# as14120_x31_fpga_ttl.net
KiCad netlist of a schematic drawn in Altium Designer
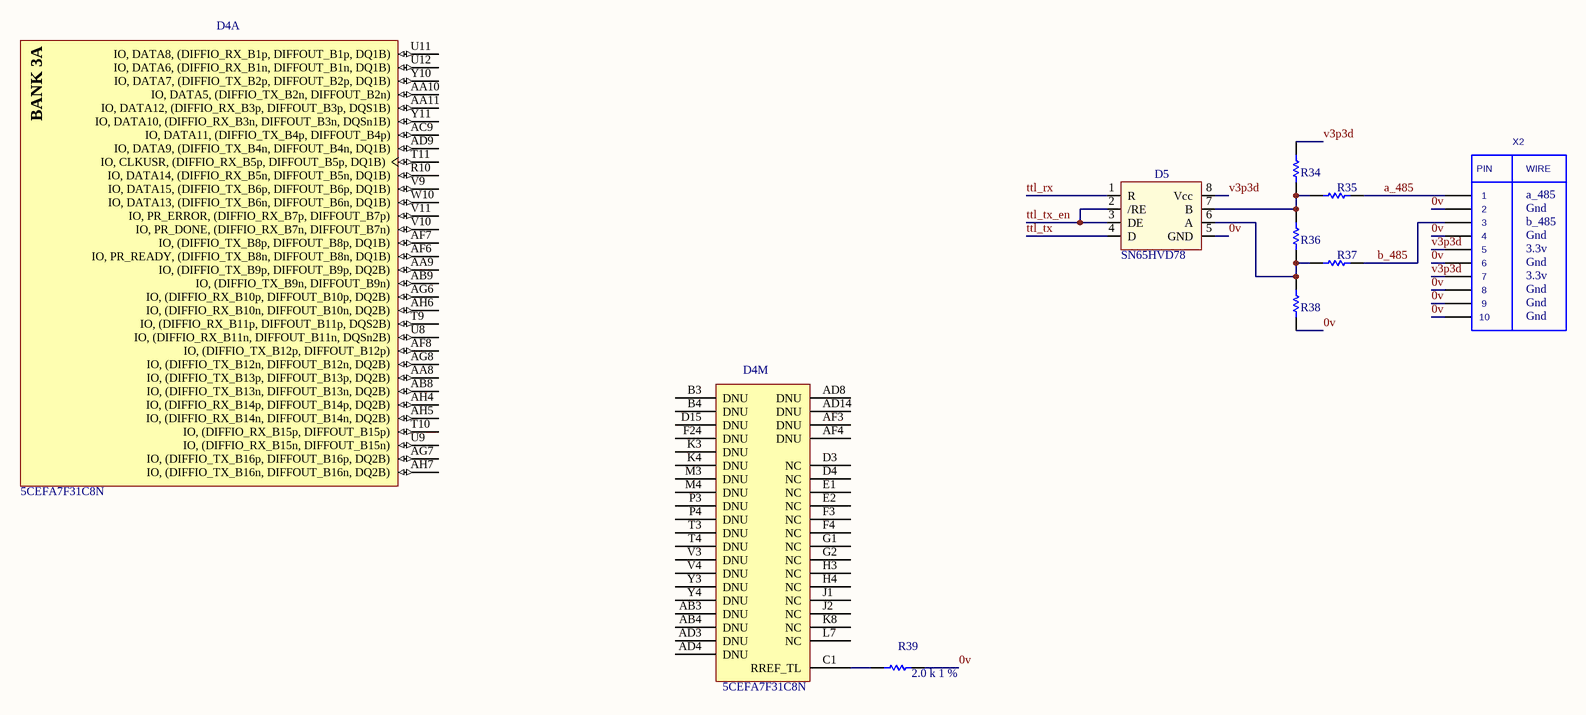
[diagram p0: as14120_x31_fpga_ttl.SchDoc]

(export (version "E")
  (design (tool "Eeschema 10.0.6"))
  (components
    (comp (ref "D4")
      (value "5CEFA7F31C8N")
      (footprint "ALTR-896-FBGA-2000A")
      (fields (field (name "MANUFACTURER") "Altera"))
      (libsource (lib "Altera Cyclone V E") (part "5CEFA7F31C8N"))
    )
    (comp (ref "D5") (value "SN65HVD78") (footprint "8S1_M") (libsource (lib "as14120") (part "SN65HVD78")))
    (comp (ref "R34")
      (value "1K 1% 0805(2012)")
      (footprint "RESC0805(2012)_L")
      (description "1K 0.125W 1% 0805 (2012 Metric)  SMD")
      (fields (field (name "TOLERANCE") "1 %") (field (name "POWER") "0.125 W"))
      (libsource (lib "as14120") (part "RES_0805"))
    )
    (comp (ref "R35")
      (value "1K 1% 0805(2012)")
      (footprint "RESC0805(2012)_L")
      (description "1K 0.125W 1% 0805 (2012 Metric)  SMD")
      (fields (field (name "TOLERANCE") "1 %") (field (name "POWER") "0.125 W"))
      (libsource (lib "as14120") (part "RES_0805"))
    )
    (comp (ref "R36")
      (value "1K 1% 0805(2012)")
      (footprint "RESC0805(2012)_L")
      (description "1K 0.125W 1% 0805 (2012 Metric)  SMD")
      (fields (field (name "TOLERANCE") "1 %") (field (name "POWER") "0.125 W"))
      (libsource (lib "as14120") (part "RES_0805"))
    )
    (comp (ref "R37")
      (value "1K 1% 0805(2012)")
      (footprint "RESC0805(2012)_L")
      (description "1K 0.125W 1% 0805 (2012 Metric)  SMD")
      (fields (field (name "TOLERANCE") "1 %") (field (name "POWER") "0.125 W"))
      (libsource (lib "as14120") (part "RES_0805"))
    )
    (comp (ref "R38")
      (value "1K 1% 0805(2012)")
      (footprint "RESC0805(2012)_L")
      (description "1K 0.125W 1% 0805 (2012 Metric)  SMD")
      (fields (field (name "TOLERANCE") "1 %") (field (name "POWER") "0.125 W"))
      (libsource (lib "as14120") (part "RES_0805"))
    )
    (comp (ref "R39")
      (value "2.0 k")
      (footprint "RESC0805(2012)_L")
      (description "1K 0.125W 1% 0805 (2012 Metric)  SMD")
      (fields
        (field (name "TOLERANCE") "1 %")
        (field (name "POWER") "0.125 W")
        (field (name "Comment") "1K 1% 0805(2012)")
      )
      (libsource (lib "as14120") (part "RES_0805"))
    )
    (comp (ref "X2") (value "IDC10") (footprint "IDC10M") (libsource (lib "alexsb") (part "IDC10")))
  )
  (nets
    (net (code "1") (name "/0v") (class "Default")
      (node (ref "D5") (pin "5") (pinfunction "GND_5") (pintype "passive"))
      (node (ref "R38") (pin "1") (pinfunction "1_1") (pintype "passive"))
      (node (ref "R39") (pin "2") (pinfunction "2_2") (pintype "passive"))
      (node (ref "X2") (pin "10") (pintype "passive"))
      (node (ref "X2") (pin "2") (pintype "passive"))
      (node (ref "X2") (pin "4") (pintype "passive"))
      (node (ref "X2") (pin "6") (pintype "passive"))
      (node (ref "X2") (pin "8") (pintype "passive"))
      (node (ref "X2") (pin "9") (pintype "passive"))
    )
    (net (code "2") (name "/a_485") (class "Default")
      (node (ref "R35") (pin "2") (pinfunction "2_2") (pintype "passive"))
      (node (ref "X2") (pin "1") (pintype "passive"))
    )
    (net (code "3") (name "/b_485") (class "Default")
      (node (ref "R37") (pin "2") (pinfunction "2_2") (pintype "passive"))
      (node (ref "X2") (pin "3") (pintype "passive"))
    )
    (net (code "4") (name "/ttl_rx") (class "Default")
      (node (ref "D5") (pin "1") (pinfunction "R_1") (pintype "passive"))
    )
    (net (code "5") (name "/ttl_tx") (class "Default")
      (node (ref "D5") (pin "4") (pinfunction "D_4") (pintype "passive"))
    )
    (net (code "6") (name "/ttl_tx_en") (class "Default")
      (node (ref "D5") (pin "2") (pinfunction "/RE_2") (pintype "passive"))
      (node (ref "D5") (pin "3") (pinfunction "DE_3") (pintype "passive"))
    )
    (net (code "7") (name "/v3p3d") (class "Default")
      (node (ref "D5") (pin "8") (pinfunction "Vcc_8") (pintype "passive"))
      (node (ref "R34") (pin "2") (pinfunction "2_2") (pintype "passive"))
      (node (ref "X2") (pin "5") (pintype "passive"))
      (node (ref "X2") (pin "7") (pintype "passive"))
    )
    (net (code "8") (name "Net-(D4M-RREF_TL)") (class "Default")
      (node (ref "D4") (pin "C1") (pinfunction "RREF_TL_C1") (pintype "passive"))
      (node (ref "R39") (pin "1") (pinfunction "1_1") (pintype "passive"))
    )
    (net (code "9") (name "Net-(D5-A)") (class "Default")
      (node (ref "D5") (pin "6") (pinfunction "A_6") (pintype "passive"))
      (node (ref "R36") (pin "1") (pinfunction "1_1") (pintype "passive"))
      (node (ref "R37") (pin "1") (pinfunction "1_1") (pintype "passive"))
      (node (ref "R38") (pin "2") (pinfunction "2_2") (pintype "passive"))
    )
    (net (code "10") (name "Net-(D5-B)") (class "Default")
      (node (ref "D5") (pin "7") (pinfunction "B_7") (pintype "passive"))
      (node (ref "R34") (pin "1") (pinfunction "1_1") (pintype "passive"))
      (node (ref "R35") (pin "1") (pinfunction "1_1") (pintype "passive"))
      (node (ref "R36") (pin "2") (pinfunction "2_2") (pintype "passive"))
    )
    (net (code "11") (name "unconnected-(D4A-IO,_(DIFFIO_RX_B10n,_DIFFOUT_B10n,_DQ2B)-PadAH6)") (class "Default")
      (node (ref "D4") (pin "AH6") (pinfunction "IO,_(DIFFIO_RX_B10n,_DIFFOUT_B10n,_DQ2B)_AH6") (pintype "bidirectional"))
    )
    (net (code "12") (name "unconnected-(D4A-IO,_(DIFFIO_RX_B10p,_DIFFOUT_B10p,_DQ2B)-PadAG6)") (class "Default")
      (node (ref "D4") (pin "AG6") (pinfunction "IO,_(DIFFIO_RX_B10p,_DIFFOUT_B10p,_DQ2B)_AG6") (pintype "bidirectional"))
    )
    (net (code "13") (name "unconnected-(D4A-IO,_(DIFFIO_RX_B11n,_DIFFOUT_B11n,_DQSn2B)-PadU8)") (class "Default")
      (node (ref "D4") (pin "U8") (pinfunction "IO,_(DIFFIO_RX_B11n,_DIFFOUT_B11n,_DQSn2B)_U8") (pintype "bidirectional"))
    )
    (net (code "14") (name "unconnected-(D4A-IO,_(DIFFIO_RX_B11p,_DIFFOUT_B11p,_DQS2B)-PadT9)") (class "Default")
      (node (ref "D4") (pin "T9") (pinfunction "IO,_(DIFFIO_RX_B11p,_DIFFOUT_B11p,_DQS2B)_T9") (pintype "bidirectional"))
    )
    (net (code "15") (name "unconnected-(D4A-IO,_(DIFFIO_RX_B14n,_DIFFOUT_B14n,_DQ2B)-PadAH5)") (class "Default")
      (node (ref "D4") (pin "AH5") (pinfunction "IO,_(DIFFIO_RX_B14n,_DIFFOUT_B14n,_DQ2B)_AH5") (pintype "bidirectional"))
    )
    (net (code "16") (name "unconnected-(D4A-IO,_(DIFFIO_RX_B14p,_DIFFOUT_B14p,_DQ2B)-PadAH4)") (class "Default")
      (node (ref "D4") (pin "AH4") (pinfunction "IO,_(DIFFIO_RX_B14p,_DIFFOUT_B14p,_DQ2B)_AH4") (pintype "bidirectional"))
    )
    (net (code "17") (name "unconnected-(D4A-IO,_(DIFFIO_RX_B15n,_DIFFOUT_B15n)-PadU9)") (class "Default")
      (node (ref "D4") (pin "U9") (pinfunction "IO,_(DIFFIO_RX_B15n,_DIFFOUT_B15n)_U9") (pintype "bidirectional"))
    )
    (net (code "18") (name "unconnected-(D4A-IO,_(DIFFIO_RX_B15p,_DIFFOUT_B15p)-PadT10)") (class "Default")
      (node (ref "D4") (pin "T10") (pinfunction "IO,_(DIFFIO_RX_B15p,_DIFFOUT_B15p)_T10") (pintype "bidirectional"))
    )
    (net (code "19") (name "unconnected-(D4A-IO,_(DIFFIO_TX_B8p,_DIFFOUT_B8p,_DQ1B)-PadAF7)") (class "Default")
      (node (ref "D4") (pin "AF7") (pinfunction "IO,_(DIFFIO_TX_B8p,_DIFFOUT_B8p,_DQ1B)_AF7") (pintype "bidirectional"))
    )
    (net (code "20") (name "unconnected-(D4A-IO,_(DIFFIO_TX_B9n,_DIFFOUT_B9n)-PadAB9)") (class "Default")
      (node (ref "D4") (pin "AB9") (pinfunction "IO,_(DIFFIO_TX_B9n,_DIFFOUT_B9n)_AB9") (pintype "bidirectional"))
    )
    (net (code "21") (name "unconnected-(D4A-IO,_(DIFFIO_TX_B9p,_DIFFOUT_B9p,_DQ2B)-PadAA9)") (class "Default")
      (node (ref "D4") (pin "AA9") (pinfunction "IO,_(DIFFIO_TX_B9p,_DIFFOUT_B9p,_DQ2B)_AA9") (pintype "bidirectional"))
    )
    (net (code "22") (name "unconnected-(D4A-IO,_(DIFFIO_TX_B12n,_DIFFOUT_B12n,_DQ2B)-PadAG8)") (class "Default")
      (node (ref "D4") (pin "AG8") (pinfunction "IO,_(DIFFIO_TX_B12n,_DIFFOUT_B12n,_DQ2B)_AG8") (pintype "bidirectional"))
    )
    (net (code "23") (name "unconnected-(D4A-IO,_(DIFFIO_TX_B12p,_DIFFOUT_B12p)-PadAF8)") (class "Default")
      (node (ref "D4") (pin "AF8") (pinfunction "IO,_(DIFFIO_TX_B12p,_DIFFOUT_B12p)_AF8") (pintype "bidirectional"))
    )
    (net (code "24") (name "unconnected-(D4A-IO,_(DIFFIO_TX_B13n,_DIFFOUT_B13n,_DQ2B)-PadAB8)") (class "Default")
      (node (ref "D4") (pin "AB8") (pinfunction "IO,_(DIFFIO_TX_B13n,_DIFFOUT_B13n,_DQ2B)_AB8") (pintype "bidirectional"))
    )
    (net (code "25") (name "unconnected-(D4A-IO,_(DIFFIO_TX_B13p,_DIFFOUT_B13p,_DQ2B)-PadAA8)") (class "Default")
      (node (ref "D4") (pin "AA8") (pinfunction "IO,_(DIFFIO_TX_B13p,_DIFFOUT_B13p,_DQ2B)_AA8") (pintype "bidirectional"))
    )
    (net (code "26") (name "unconnected-(D4A-IO,_(DIFFIO_TX_B16n,_DIFFOUT_B16n,_DQ2B)-PadAH7)") (class "Default")
      (node (ref "D4") (pin "AH7") (pinfunction "IO,_(DIFFIO_TX_B16n,_DIFFOUT_B16n,_DQ2B)_AH7") (pintype "bidirectional"))
    )
    (net (code "27") (name "unconnected-(D4A-IO,_(DIFFIO_TX_B16p,_DIFFOUT_B16p,_DQ2B)-PadAG7)") (class "Default")
      (node (ref "D4") (pin "AG7") (pinfunction "IO,_(DIFFIO_TX_B16p,_DIFFOUT_B16p,_DQ2B)_AG7") (pintype "bidirectional"))
    )
    (net (code "28") (name "unconnected-(D4A-IO,_CLKUSR,_(DIFFIO_RX_B5p,_DIFFOUT_B5p,_DQ1B)-PadT11)") (class "Default")
      (node (ref "D4") (pin "T11") (pinfunction "IO,_CLKUSR,_(DIFFIO_RX_B5p,_DIFFOUT_B5p,_DQ1B)_T11") (pintype "bidirectional"))
    )
    (net (code "29") (name "unconnected-(D4A-IO,_DATA5,_(DIFFIO_TX_B2n,_DIFFOUT_B2n)-PadAA10)") (class "Default")
      (node (ref "D4") (pin "AA10") (pinfunction "IO,_DATA5,_(DIFFIO_TX_B2n,_DIFFOUT_B2n)_AA10") (pintype "bidirectional"))
    )
    (net (code "30") (name "unconnected-(D4A-IO,_DATA6,_(DIFFIO_RX_B1n,_DIFFOUT_B1n,_DQ1B)-PadU12)") (class "Default")
      (node (ref "D4") (pin "U12") (pinfunction "IO,_DATA6,_(DIFFIO_RX_B1n,_DIFFOUT_B1n,_DQ1B)_U12") (pintype "bidirectional"))
    )
    (net (code "31") (name "unconnected-(D4A-IO,_DATA7,_(DIFFIO_TX_B2p,_DIFFOUT_B2p,_DQ1B)-PadY10)") (class "Default")
      (node (ref "D4") (pin "Y10") (pinfunction "IO,_DATA7,_(DIFFIO_TX_B2p,_DIFFOUT_B2p,_DQ1B)_Y10") (pintype "bidirectional"))
    )
    (net (code "32") (name "unconnected-(D4A-IO,_DATA8,_(DIFFIO_RX_B1p,_DIFFOUT_B1p,_DQ1B)-PadU11)") (class "Default")
      (node (ref "D4") (pin "U11") (pinfunction "IO,_DATA8,_(DIFFIO_RX_B1p,_DIFFOUT_B1p,_DQ1B)_U11") (pintype "bidirectional"))
    )
    (net (code "33") (name "unconnected-(D4A-IO,_DATA9,_(DIFFIO_TX_B4n,_DIFFOUT_B4n,_DQ1B)-PadAD9)") (class "Default")
      (node (ref "D4") (pin "AD9") (pinfunction "IO,_DATA9,_(DIFFIO_TX_B4n,_DIFFOUT_B4n,_DQ1B)_AD9") (pintype "bidirectional"))
    )
    (net (code "34") (name "unconnected-(D4A-IO,_DATA10,_(DIFFIO_RX_B3n,_DIFFOUT_B3n,_DQSn1B)-PadY11)") (class "Default")
      (node (ref "D4") (pin "Y11") (pinfunction "IO,_DATA10,_(DIFFIO_RX_B3n,_DIFFOUT_B3n,_DQSn1B)_Y11") (pintype "bidirectional"))
    )
    (net (code "35") (name "unconnected-(D4A-IO,_DATA11,_(DIFFIO_TX_B4p,_DIFFOUT_B4p)-PadAC9)") (class "Default")
      (node (ref "D4") (pin "AC9") (pinfunction "IO,_DATA11,_(DIFFIO_TX_B4p,_DIFFOUT_B4p)_AC9") (pintype "bidirectional"))
    )
    (net (code "36") (name "unconnected-(D4A-IO,_DATA12,_(DIFFIO_RX_B3p,_DIFFOUT_B3p,_DQS1B)-PadAA11)") (class "Default")
      (node (ref "D4") (pin "AA11") (pinfunction "IO,_DATA12,_(DIFFIO_RX_B3p,_DIFFOUT_B3p,_DQS1B)_AA11") (pintype "bidirectional"))
    )
    (net (code "37") (name "unconnected-(D4A-IO,_DATA13,_(DIFFIO_TX_B6n,_DIFFOUT_B6n,_DQ1B)-PadW10)") (class "Default")
      (node (ref "D4") (pin "W10") (pinfunction "IO,_DATA13,_(DIFFIO_TX_B6n,_DIFFOUT_B6n,_DQ1B)_W10") (pintype "bidirectional"))
    )
    (net (code "38") (name "unconnected-(D4A-IO,_DATA14,_(DIFFIO_RX_B5n,_DIFFOUT_B5n,_DQ1B)-PadR10)") (class "Default")
      (node (ref "D4") (pin "R10") (pinfunction "IO,_DATA14,_(DIFFIO_RX_B5n,_DIFFOUT_B5n,_DQ1B)_R10") (pintype "bidirectional"))
    )
    (net (code "39") (name "unconnected-(D4A-IO,_DATA15,_(DIFFIO_TX_B6p,_DIFFOUT_B6p,_DQ1B)-PadV9)") (class "Default")
      (node (ref "D4") (pin "V9") (pinfunction "IO,_DATA15,_(DIFFIO_TX_B6p,_DIFFOUT_B6p,_DQ1B)_V9") (pintype "bidirectional"))
    )
    (net (code "40") (name "unconnected-(D4A-IO,_PR_DONE,_(DIFFIO_RX_B7n,_DIFFOUT_B7n)-PadV10)") (class "Default")
      (node (ref "D4") (pin "V10") (pinfunction "IO,_PR_DONE,_(DIFFIO_RX_B7n,_DIFFOUT_B7n)_V10") (pintype "bidirectional"))
    )
    (net (code "41") (name "unconnected-(D4A-IO,_PR_ERROR,_(DIFFIO_RX_B7p,_DIFFOUT_B7p)-PadV11)") (class "Default")
      (node (ref "D4") (pin "V11") (pinfunction "IO,_PR_ERROR,_(DIFFIO_RX_B7p,_DIFFOUT_B7p)_V11") (pintype "bidirectional"))
    )
    (net (code "42") (name "unconnected-(D4A-IO,_PR_READY,_(DIFFIO_TX_B8n,_DIFFOUT_B8n,_DQ1B)-PadAF6)") (class "Default")
      (node (ref "D4") (pin "AF6") (pinfunction "IO,_PR_READY,_(DIFFIO_TX_B8n,_DIFFOUT_B8n,_DQ1B)_AF6") (pintype "bidirectional"))
    )
    (net (code "43") (name "unconnected-(D4M-DNU-PadAB3)") (class "Default")
      (node (ref "D4") (pin "AB3") (pinfunction "DNU_AB3") (pintype "passive"))
    )
    (net (code "44") (name "unconnected-(D4M-DNU-PadAB4)") (class "Default")
      (node (ref "D4") (pin "AB4") (pinfunction "DNU_AB4") (pintype "passive"))
    )
    (net (code "45") (name "unconnected-(D4M-DNU-PadAD3)") (class "Default")
      (node (ref "D4") (pin "AD3") (pinfunction "DNU_AD3") (pintype "passive"))
    )
    (net (code "46") (name "unconnected-(D4M-DNU-PadAD4)") (class "Default")
      (node (ref "D4") (pin "AD4") (pinfunction "DNU_AD4") (pintype "passive"))
    )
    (net (code "47") (name "unconnected-(D4M-DNU-PadAD8)") (class "Default")
      (node (ref "D4") (pin "AD8") (pinfunction "DNU_AD8") (pintype "passive"))
    )
    (net (code "48") (name "unconnected-(D4M-DNU-PadAD14)") (class "Default")
      (node (ref "D4") (pin "AD14") (pinfunction "DNU_AD14") (pintype "passive"))
    )
    (net (code "49") (name "unconnected-(D4M-DNU-PadAF3)") (class "Default")
      (node (ref "D4") (pin "AF3") (pinfunction "DNU_AF3") (pintype "passive"))
    )
    (net (code "50") (name "unconnected-(D4M-DNU-PadAF4)") (class "Default")
      (node (ref "D4") (pin "AF4") (pinfunction "DNU_AF4") (pintype "passive"))
    )
    (net (code "51") (name "unconnected-(D4M-DNU-PadB3)") (class "Default")
      (node (ref "D4") (pin "B3") (pinfunction "DNU_B3") (pintype "passive"))
    )
    (net (code "52") (name "unconnected-(D4M-DNU-PadB4)") (class "Default")
      (node (ref "D4") (pin "B4") (pinfunction "DNU_B4") (pintype "passive"))
    )
    (net (code "53") (name "unconnected-(D4M-DNU-PadD15)") (class "Default")
      (node (ref "D4") (pin "D15") (pinfunction "DNU_D15") (pintype "passive"))
    )
    (net (code "54") (name "unconnected-(D4M-DNU-PadF24)") (class "Default")
      (node (ref "D4") (pin "F24") (pinfunction "DNU_F24") (pintype "passive"))
    )
    (net (code "55") (name "unconnected-(D4M-DNU-PadK3)") (class "Default")
      (node (ref "D4") (pin "K3") (pinfunction "DNU_K3") (pintype "passive"))
    )
    (net (code "56") (name "unconnected-(D4M-DNU-PadK4)") (class "Default")
      (node (ref "D4") (pin "K4") (pinfunction "DNU_K4") (pintype "passive"))
    )
    (net (code "57") (name "unconnected-(D4M-DNU-PadM3)") (class "Default")
      (node (ref "D4") (pin "M3") (pinfunction "DNU_M3") (pintype "passive"))
    )
    (net (code "58") (name "unconnected-(D4M-DNU-PadM4)") (class "Default")
      (node (ref "D4") (pin "M4") (pinfunction "DNU_M4") (pintype "passive"))
    )
    (net (code "59") (name "unconnected-(D4M-DNU-PadP3)") (class "Default")
      (node (ref "D4") (pin "P3") (pinfunction "DNU_P3") (pintype "passive"))
    )
    (net (code "60") (name "unconnected-(D4M-DNU-PadP4)") (class "Default")
      (node (ref "D4") (pin "P4") (pinfunction "DNU_P4") (pintype "passive"))
    )
    (net (code "61") (name "unconnected-(D4M-DNU-PadT3)") (class "Default")
      (node (ref "D4") (pin "T3") (pinfunction "DNU_T3") (pintype "passive"))
    )
    (net (code "62") (name "unconnected-(D4M-DNU-PadT4)") (class "Default")
      (node (ref "D4") (pin "T4") (pinfunction "DNU_T4") (pintype "passive"))
    )
    (net (code "63") (name "unconnected-(D4M-DNU-PadV3)") (class "Default")
      (node (ref "D4") (pin "V3") (pinfunction "DNU_V3") (pintype "passive"))
    )
    (net (code "64") (name "unconnected-(D4M-DNU-PadV4)") (class "Default")
      (node (ref "D4") (pin "V4") (pinfunction "DNU_V4") (pintype "passive"))
    )
    (net (code "65") (name "unconnected-(D4M-DNU-PadY3)") (class "Default")
      (node (ref "D4") (pin "Y3") (pinfunction "DNU_Y3") (pintype "passive"))
    )
    (net (code "66") (name "unconnected-(D4M-DNU-PadY4)") (class "Default")
      (node (ref "D4") (pin "Y4") (pinfunction "DNU_Y4") (pintype "passive"))
    )
    (net (code "67") (name "unconnected-(D4M-NC-PadD3)") (class "Default")
      (node (ref "D4") (pin "D3") (pinfunction "NC_D3") (pintype "passive"))
    )
    (net (code "68") (name "unconnected-(D4M-NC-PadD4)") (class "Default")
      (node (ref "D4") (pin "D4") (pinfunction "NC_D4") (pintype "passive"))
    )
    (net (code "69") (name "unconnected-(D4M-NC-PadE1)") (class "Default")
      (node (ref "D4") (pin "E1") (pinfunction "NC_E1") (pintype "passive"))
    )
    (net (code "70") (name "unconnected-(D4M-NC-PadE2)") (class "Default")
      (node (ref "D4") (pin "E2") (pinfunction "NC_E2") (pintype "passive"))
    )
    (net (code "71") (name "unconnected-(D4M-NC-PadF3)") (class "Default")
      (node (ref "D4") (pin "F3") (pinfunction "NC_F3") (pintype "passive"))
    )
    (net (code "72") (name "unconnected-(D4M-NC-PadF4)") (class "Default")
      (node (ref "D4") (pin "F4") (pinfunction "NC_F4") (pintype "passive"))
    )
    (net (code "73") (name "unconnected-(D4M-NC-PadG1)") (class "Default")
      (node (ref "D4") (pin "G1") (pinfunction "NC_G1") (pintype "passive"))
    )
    (net (code "74") (name "unconnected-(D4M-NC-PadG2)") (class "Default")
      (node (ref "D4") (pin "G2") (pinfunction "NC_G2") (pintype "passive"))
    )
    (net (code "75") (name "unconnected-(D4M-NC-PadH3)") (class "Default")
      (node (ref "D4") (pin "H3") (pinfunction "NC_H3") (pintype "passive"))
    )
    (net (code "76") (name "unconnected-(D4M-NC-PadH4)") (class "Default")
      (node (ref "D4") (pin "H4") (pinfunction "NC_H4") (pintype "passive"))
    )
    (net (code "77") (name "unconnected-(D4M-NC-PadJ1)") (class "Default")
      (node (ref "D4") (pin "J1") (pinfunction "NC_J1") (pintype "passive"))
    )
    (net (code "78") (name "unconnected-(D4M-NC-PadJ2)") (class "Default")
      (node (ref "D4") (pin "J2") (pinfunction "NC_J2") (pintype "passive"))
    )
    (net (code "79") (name "unconnected-(D4M-NC-PadK8)") (class "Default")
      (node (ref "D4") (pin "K8") (pinfunction "NC_K8") (pintype "passive"))
    )
    (net (code "80") (name "unconnected-(D4M-NC-PadL7)") (class "Default")
      (node (ref "D4") (pin "L7") (pinfunction "NC_L7") (pintype "passive"))
    )
  )
)
